# Communicate.net
KiCad netlist of a schematic drawn in Altium Designer
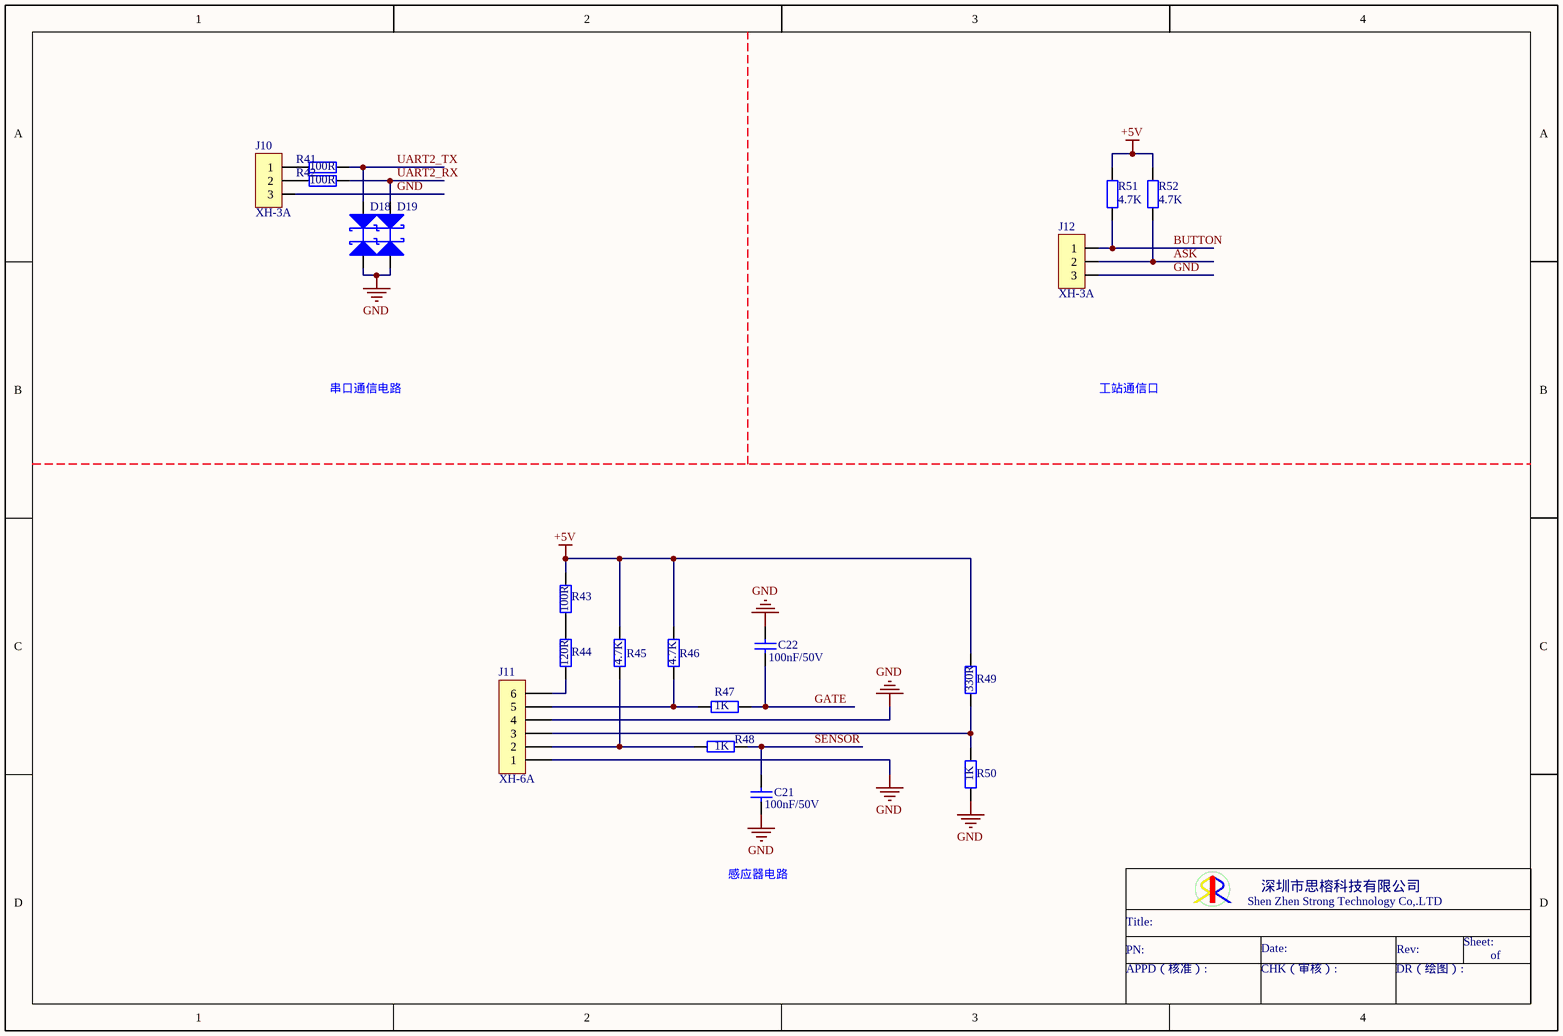
[diagram p0: Communicate.SchDoc]

(export (version "E")
  (design (tool "Eeschema 10.0.6"))
  (components
    (comp (ref "C21")
      (value "100nF/50V")
      (footprint "0603C")
      (description "瓷片电容,100nF,5%,X7R,50V,0603")
      (libsource (lib "SR SCH Library V02") (part "C100nF/50V-0603"))
    )
    (comp (ref "C22")
      (value "100nF/50V")
      (footprint "0603C")
      (description "瓷片电容,100nF,5%,X7R,50V,0603")
      (libsource (lib "SR SCH Library V02") (part "C100nF/50V-0603"))
    )
    (comp (ref "D18")
      (value "ESD5B5.0ST1G")
      (footprint "SOD-523")
      (description "TVS管,5V,SOD-523")
      (libsource (lib "SR SCH Library V02") (part "ESD5B5.0ST1G"))
    )
    (comp (ref "D19")
      (value "ESD5B5.0ST1G")
      (footprint "SOD-523")
      (description "TVS管,5V,SOD-523")
      (libsource (lib "SR SCH Library V02") (part "ESD5B5.0ST1G"))
    )
    (comp (ref "J10")
      (value "XH-3A")
      (footprint "CN3-2.54")
      (description "CONN,XH-3A,3PIN,2.54mm插座")
      (libsource (lib "SR SCH Library V02") (part "CONN-XH-3A"))
    )
    (comp (ref "J11")
      (value "XH-6A")
      (footprint "CN6-2.54")
      (description "CONN,XH-6A,6PIN,2.54mm插座")
      (libsource (lib "SR SCH Library V02") (part "CONN-XH-6A"))
    )
    (comp (ref "J12")
      (value "XH-3A")
      (footprint "CN3-2.54")
      (description "CONN,XH-3A,3PIN,2.54mm插座")
      (libsource (lib "SR SCH Library V02") (part "CONN-XH-3A"))
    )
    (comp (ref "R41")
      (value "100R")
      (footprint "0603R")
      (description "金属膜电阻,100R,1%,1/10W,0603")
      (libsource (lib "SR SCH Library V02") (part "R100R-0603"))
    )
    (comp (ref "R42")
      (value "100R")
      (footprint "0603R")
      (description "金属膜电阻,100R,1%,1/10W,0603")
      (libsource (lib "SR SCH Library V02") (part "R100R-0603"))
    )
    (comp (ref "R43")
      (value "100R")
      (footprint "0603R")
      (description "金属膜电阻,100R,1%,1/10W,0603")
      (libsource (lib "") (part "R100R-0603_1"))
    )
    (comp (ref "R44")
      (value "120R")
      (footprint "0603R")
      (description "金属膜电阻,120R,5W,5%")
      (libsource (lib "SR SCH Library V02") (part "R120R"))
    )
    (comp (ref "R45")
      (value "4.7K")
      (footprint "0603R")
      (description "金属膜电阻,4.7K,1%,1/10W,0603")
      (libsource (lib "SR SCH Library V02") (part "R4.7K-0603"))
    )
    (comp (ref "R46")
      (value "4.7K")
      (footprint "0603R")
      (description "金属膜电阻,4.7K,1%,1/10W,0603")
      (libsource (lib "SR SCH Library V02") (part "R4.7K-0603"))
    )
    (comp (ref "R47")
      (value "1K")
      (footprint "0603R")
      (description "金属膜电阻,1K,1%,1/10W,0603")
      (libsource (lib "") (part "R1K-0603_1"))
    )
    (comp (ref "R48")
      (value "1K")
      (footprint "0603R")
      (description "金属膜电阻,1K,1%,1/10W,0603")
      (libsource (lib "") (part "R1K-0603_1"))
    )
    (comp (ref "R49")
      (value "330R")
      (footprint "0603R")
      (description "金属膜电阻,330R,1%,1/10W,0603")
      (libsource (lib "SR SCH Library V02") (part "R330R-0603"))
    )
    (comp (ref "R50")
      (value "1K")
      (footprint "0603R")
      (description "金属膜电阻,1K,1%,1/10W,0603")
      (libsource (lib "SR SCH Library V02") (part "R1K-0603"))
    )
    (comp (ref "R51")
      (value "4.7K")
      (footprint "0603R")
      (description "金属膜电阻,4.7K,1%,1/10W,0603")
      (libsource (lib "SR SCH Library V02") (part "R4.7K-0603"))
    )
    (comp (ref "R52")
      (value "4.7K")
      (footprint "0603R")
      (description "金属膜电阻,4.7K,1%,1/10W,0603")
      (libsource (lib "SR SCH Library V02") (part "R4.7K-0603"))
    )
  )
  (nets
    (net (code "1") (name "+5V") (class "Default")
      (node (ref "R43") (pin "2") (pinfunction "2_2") (pintype "passive"))
      (node (ref "R45") (pin "2") (pinfunction "2_2") (pintype "passive"))
      (node (ref "R46") (pin "2") (pinfunction "2_2") (pintype "passive"))
      (node (ref "R49") (pin "2") (pinfunction "2_2") (pintype "passive"))
      (node (ref "R51") (pin "2") (pinfunction "2_2") (pintype "passive"))
      (node (ref "R52") (pin "2") (pinfunction "2_2") (pintype "passive"))
    )
    (net (code "2") (name "/ASK") (class "Default")
      (node (ref "J12") (pin "2") (pinfunction "2_2") (pintype "passive"))
      (node (ref "R52") (pin "1") (pinfunction "1_1") (pintype "passive"))
    )
    (net (code "3") (name "/BUTTON") (class "Default")
      (node (ref "J12") (pin "1") (pinfunction "1_1") (pintype "passive"))
      (node (ref "R51") (pin "1") (pinfunction "1_1") (pintype "passive"))
    )
    (net (code "4") (name "/GATE") (class "Default")
      (node (ref "C22") (pin "2") (pinfunction "2_2") (pintype "passive"))
      (node (ref "R47") (pin "2") (pinfunction "2_2") (pintype "passive"))
    )
    (net (code "5") (name "/SENSOR") (class "Default")
      (node (ref "C21") (pin "2") (pinfunction "2_2") (pintype "passive"))
      (node (ref "R48") (pin "2") (pinfunction "2_2") (pintype "passive"))
    )
    (net (code "6") (name "/UART2_RX") (class "Default")
      (node (ref "D19") (pin "2") (pinfunction "2_2") (pintype "passive"))
      (node (ref "R42") (pin "2") (pinfunction "2_2") (pintype "passive"))
    )
    (net (code "7") (name "/UART2_TX") (class "Default")
      (node (ref "D18") (pin "2") (pinfunction "2_2") (pintype "passive"))
      (node (ref "R41") (pin "2") (pinfunction "2_2") (pintype "passive"))
    )
    (net (code "8") (name "GND") (class "Default")
      (node (ref "C21") (pin "1") (pinfunction "1_1") (pintype "passive"))
      (node (ref "C22") (pin "1") (pinfunction "1_1") (pintype "passive"))
      (node (ref "D18") (pin "1") (pinfunction "1_1") (pintype "passive"))
      (node (ref "D19") (pin "1") (pinfunction "1_1") (pintype "passive"))
      (node (ref "J10") (pin "3") (pinfunction "3_3") (pintype "passive"))
      (node (ref "J11") (pin "1") (pinfunction "1_1") (pintype "passive"))
      (node (ref "J11") (pin "4") (pinfunction "4_4") (pintype "passive"))
      (node (ref "J12") (pin "3") (pinfunction "3_3") (pintype "passive"))
      (node (ref "R50") (pin "1") (pinfunction "1_1") (pintype "passive"))
    )
    (net (code "9") (name "Net-(J10-Pad1)") (class "Default")
      (node (ref "J10") (pin "1") (pinfunction "1_1") (pintype "passive"))
      (node (ref "R41") (pin "1") (pinfunction "1_1") (pintype "passive"))
    )
    (net (code "10") (name "Net-(J10-Pad2)") (class "Default")
      (node (ref "J10") (pin "2") (pinfunction "2_2") (pintype "passive"))
      (node (ref "R42") (pin "1") (pinfunction "1_1") (pintype "passive"))
    )
    (net (code "11") (name "Net-(J11-Pad2)") (class "Default")
      (node (ref "J11") (pin "2") (pinfunction "2_2") (pintype "passive"))
      (node (ref "R45") (pin "1") (pinfunction "1_1") (pintype "passive"))
      (node (ref "R48") (pin "1") (pinfunction "1_1") (pintype "passive"))
    )
    (net (code "12") (name "Net-(J11-Pad3)") (class "Default")
      (node (ref "J11") (pin "3") (pinfunction "3_3") (pintype "passive"))
      (node (ref "R49") (pin "1") (pinfunction "1_1") (pintype "passive"))
      (node (ref "R50") (pin "2") (pinfunction "2_2") (pintype "passive"))
    )
    (net (code "13") (name "Net-(J11-Pad5)") (class "Default")
      (node (ref "J11") (pin "5") (pinfunction "5_5") (pintype "passive"))
      (node (ref "R46") (pin "1") (pinfunction "1_1") (pintype "passive"))
      (node (ref "R47") (pin "1") (pinfunction "1_1") (pintype "passive"))
    )
    (net (code "14") (name "Net-(J11-Pad6)") (class "Default")
      (node (ref "J11") (pin "6") (pinfunction "6_6") (pintype "passive"))
      (node (ref "R44") (pin "1") (pinfunction "1_1") (pintype "passive"))
    )
    (net (code "15") (name "Net-(R43-Pad1)") (class "Default")
      (node (ref "R43") (pin "1") (pinfunction "1_1") (pintype "passive"))
      (node (ref "R44") (pin "2") (pinfunction "2_2") (pintype "passive"))
    )
  )
)
